# TransientsControls.net
KiCad netlist of a schematic drawn in EAGLE
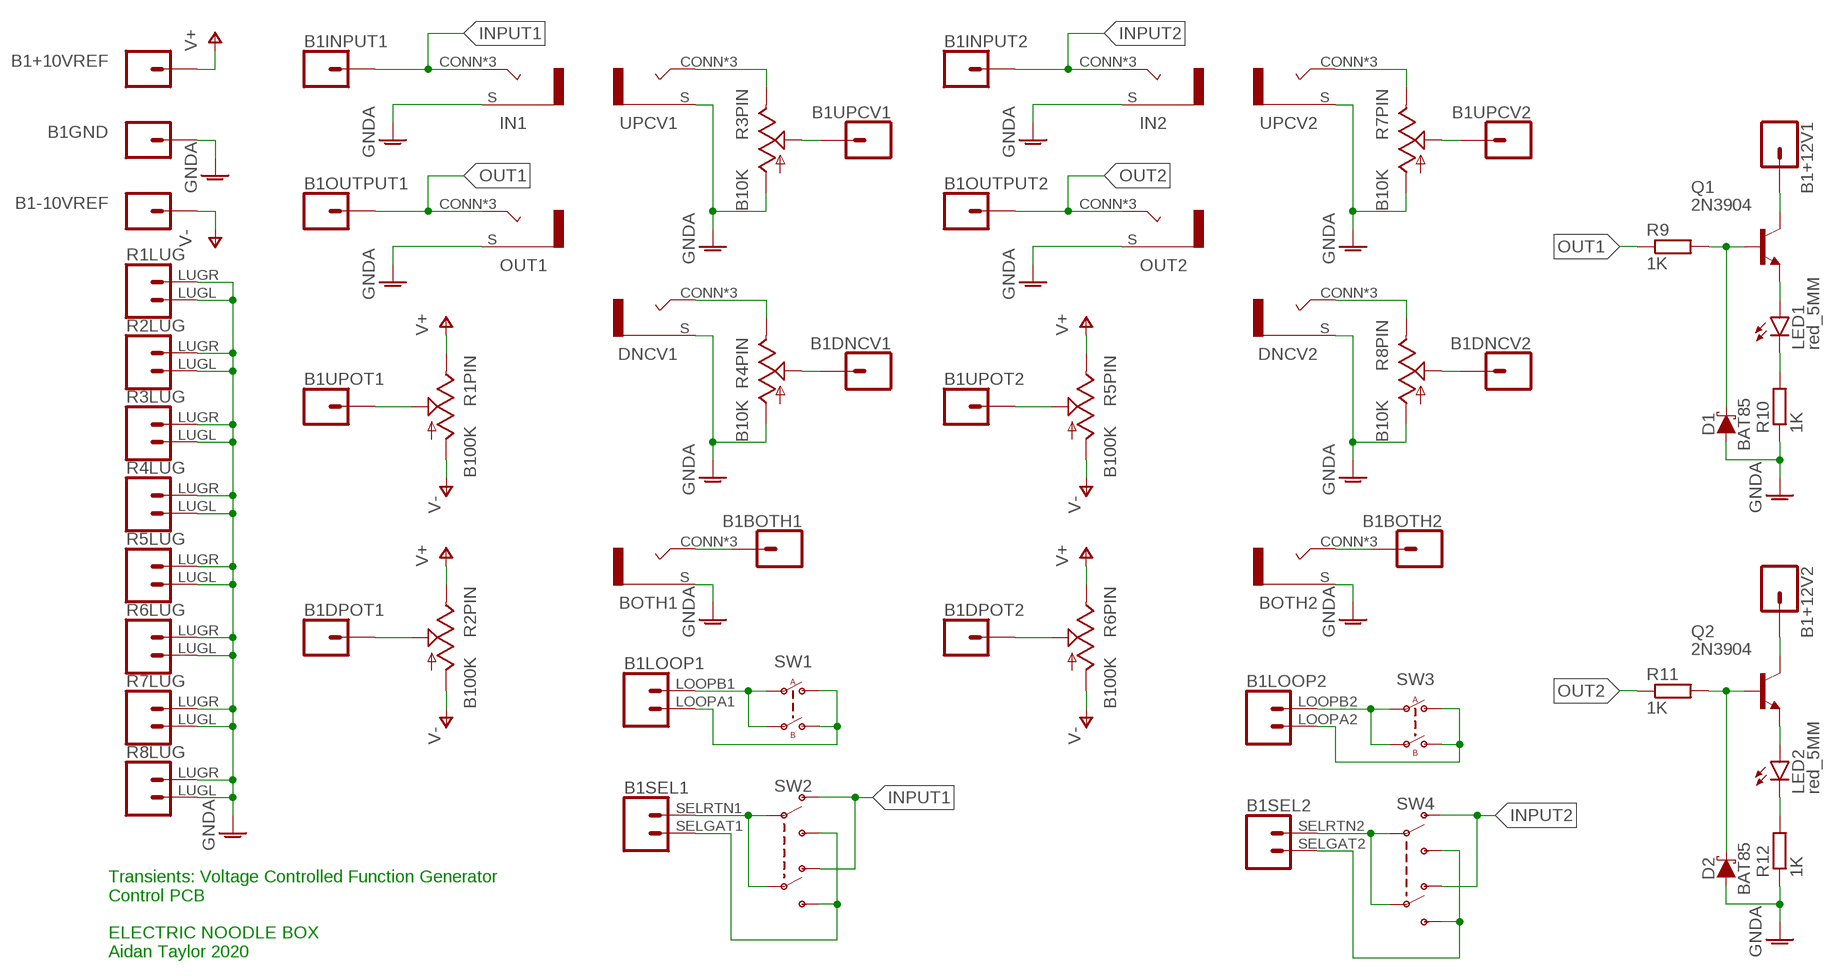
[diagram p0: schematic, sheet 1]

(export (version "E")
  (design (tool "Eeschema 10.0.6"))
  (components
    (comp (ref "B1")
      (value "TRANSIENTS_LINK")
      (footprint "eagle-import:TRANSIENTS")
      (libsource (lib "eagle-import") (part "TRANSIENTS_LINK"))
    )
    (comp (ref "BOTH1")
      (value "COMBI-JACKCINCHNANA")
      (footprint "eagle-import:NEWCOMBOJACK_PANEL")
      (libsource (lib "eagle-import") (part "COMBI-JACKCINCHNANA"))
    )
    (comp (ref "BOTH2")
      (value "COMBI-JACKCINCHNANA")
      (footprint "eagle-import:NEWCOMBOJACK_PANEL")
      (libsource (lib "eagle-import") (part "COMBI-JACKCINCHNANA"))
    )
    (comp (ref "D1")
      (value "BAT85")
      (footprint "eagle-import:DO35-7")
      (libsource (lib "eagle-import") (part "SCHOTTKY_DO35"))
    )
    (comp (ref "D2")
      (value "BAT85")
      (footprint "eagle-import:DO35-7")
      (libsource (lib "eagle-import") (part "SCHOTTKY_DO35"))
    )
    (comp (ref "DNCV1")
      (value "COMBI-JACKCINCHNANA")
      (footprint "eagle-import:NEWCOMBOJACK_PANEL")
      (libsource (lib "eagle-import") (part "COMBI-JACKCINCHNANA"))
    )
    (comp (ref "DNCV2")
      (value "COMBI-JACKCINCHNANA")
      (footprint "eagle-import:NEWCOMBOJACK_PANEL")
      (libsource (lib "eagle-import") (part "COMBI-JACKCINCHNANA"))
    )
    (comp (ref "IN1")
      (value "COMBI-JACKCINCHNANA")
      (footprint "eagle-import:NEWCOMBOJACK_PANEL")
      (libsource (lib "eagle-import") (part "COMBI-JACKCINCHNANA"))
    )
    (comp (ref "IN2")
      (value "COMBI-JACKCINCHNANA")
      (footprint "eagle-import:NEWCOMBOJACK_PANEL")
      (libsource (lib "eagle-import") (part "COMBI-JACKCINCHNANA"))
    )
    (comp (ref "LED1")
      (value "red_5MM")
      (footprint "eagle-import:LED5MM")
      (libsource (lib "eagle-import") (part "LED5MM"))
    )
    (comp (ref "LED2")
      (value "red_5MM")
      (footprint "eagle-import:LED5MM")
      (libsource (lib "eagle-import") (part "LED5MM"))
    )
    (comp (ref "OUT1")
      (value "COMBI-JACKCINCHNANA")
      (footprint "eagle-import:NEWCOMBOJACK_PANEL")
      (libsource (lib "eagle-import") (part "COMBI-JACKCINCHNANA"))
    )
    (comp (ref "OUT2")
      (value "COMBI-JACKCINCHNANA")
      (footprint "eagle-import:NEWCOMBOJACK_PANEL")
      (libsource (lib "eagle-import") (part "COMBI-JACKCINCHNANA"))
    )
    (comp (ref "Q1")
      (value "2N3904")
      (footprint "eagle-import:TO92")
      (libsource (lib "eagle-import") (part "2N3904"))
    )
    (comp (ref "Q2")
      (value "2N3904")
      (footprint "eagle-import:TO92")
      (libsource (lib "eagle-import") (part "2N3904"))
    )
    (comp (ref "R1")
      (value "B100K")
      (footprint "eagle-import:ALPHA_RV09_9MMPOT")
      (libsource (lib "eagle-import") (part "POTENTIOMETER"))
    )
    (comp (ref "R2")
      (value "B100K")
      (footprint "eagle-import:ALPHA_RV09_9MMPOT")
      (libsource (lib "eagle-import") (part "POTENTIOMETER"))
    )
    (comp (ref "R3")
      (value "B10K")
      (footprint "eagle-import:ALPHA_RV09_9MMPOT")
      (libsource (lib "eagle-import") (part "POTENTIOMETER"))
    )
    (comp (ref "R4")
      (value "B10K")
      (footprint "eagle-import:ALPHA_RV09_9MMPOT")
      (libsource (lib "eagle-import") (part "POTENTIOMETER"))
    )
    (comp (ref "R5")
      (value "B100K")
      (footprint "eagle-import:ALPHA_RV09_9MMPOT")
      (libsource (lib "eagle-import") (part "POTENTIOMETER"))
    )
    (comp (ref "R6")
      (value "B100K")
      (footprint "eagle-import:ALPHA_RV09_9MMPOT")
      (libsource (lib "eagle-import") (part "POTENTIOMETER"))
    )
    (comp (ref "R7")
      (value "B10K")
      (footprint "eagle-import:ALPHA_RV09_9MMPOT")
      (libsource (lib "eagle-import") (part "POTENTIOMETER"))
    )
    (comp (ref "R8")
      (value "B10K")
      (footprint "eagle-import:ALPHA_RV09_9MMPOT")
      (libsource (lib "eagle-import") (part "POTENTIOMETER"))
    )
    (comp (ref "R9")
      (value "1K")
      (footprint "eagle-import:0207_10")
      (libsource (lib "eagle-import") (part "R-EU_0207/10"))
    )
    (comp (ref "R10")
      (value "1K")
      (footprint "eagle-import:0207_10")
      (libsource (lib "eagle-import") (part "R-EU_0207/10"))
    )
    (comp (ref "R11")
      (value "1K")
      (footprint "eagle-import:0207_10")
      (libsource (lib "eagle-import") (part "R-EU_0207/10"))
    )
    (comp (ref "R12")
      (value "1K")
      (footprint "eagle-import:0207_10")
      (libsource (lib "eagle-import") (part "R-EU_0207/10"))
    )
    (comp (ref "SW1")
      (value "PVA1_DPST")
      (footprint "eagle-import:PVA1_PUSHBUTTON")
      (libsource (lib "eagle-import") (part "PVA1_DPST"))
    )
    (comp (ref "SW2")
      (value "PVA2_DPDT")
      (footprint "eagle-import:PVA2_PUSHBUTTON")
      (libsource (lib "eagle-import") (part "PVA2_DPDT"))
    )
    (comp (ref "SW3")
      (value "PVA1_DPST")
      (footprint "eagle-import:PVA1_PUSHBUTTON")
      (libsource (lib "eagle-import") (part "PVA1_DPST"))
    )
    (comp (ref "SW4")
      (value "PVA2_DPDT")
      (footprint "eagle-import:PVA2_PUSHBUTTON")
      (libsource (lib "eagle-import") (part "PVA2_DPDT"))
    )
    (comp (ref "UPCV1")
      (value "COMBI-JACKCINCHNANA")
      (footprint "eagle-import:NEWCOMBOJACK_PANEL")
      (libsource (lib "eagle-import") (part "COMBI-JACKCINCHNANA"))
    )
    (comp (ref "UPCV2")
      (value "COMBI-JACKCINCHNANA")
      (footprint "eagle-import:NEWCOMBOJACK_PANEL")
      (libsource (lib "eagle-import") (part "COMBI-JACKCINCHNANA"))
    )
  )
  (nets
    (net (code "1") (name "GNDA") (class "Default")
      (node (ref "B1") (pin "GND1") (pinfunction "1_GND1") (pintype "passive"))
      (node (ref "B1") (pin "GND2") (pinfunction "1_GND2") (pintype "passive"))
      (node (ref "BOTH1") (pin "S") (pinfunction "S_S") (pintype "passive"))
      (node (ref "BOTH2") (pin "S") (pinfunction "S_S") (pintype "passive"))
      (node (ref "D1") (pin "A") (pinfunction "A_A") (pintype "passive"))
      (node (ref "D2") (pin "A") (pinfunction "A_A") (pintype "passive"))
      (node (ref "DNCV1") (pin "S") (pinfunction "S_S") (pintype "passive"))
      (node (ref "DNCV2") (pin "S") (pinfunction "S_S") (pintype "passive"))
      (node (ref "IN1") (pin "S") (pinfunction "S_S") (pintype "passive"))
      (node (ref "IN2") (pin "S") (pinfunction "S_S") (pintype "passive"))
      (node (ref "OUT1") (pin "S") (pinfunction "S_S") (pintype "passive"))
      (node (ref "OUT2") (pin "S") (pinfunction "S_S") (pintype "passive"))
      (node (ref "R1") (pin "LUGL") (pinfunction "1_LUGL") (pintype "passive"))
      (node (ref "R1") (pin "LUGR") (pinfunction "2_LUGR") (pintype "passive"))
      (node (ref "R10") (pin "1") (pinfunction "1_1") (pintype "passive"))
      (node (ref "R12") (pin "1") (pinfunction "1_1") (pintype "passive"))
      (node (ref "R2") (pin "LUGL") (pinfunction "1_LUGL") (pintype "passive"))
      (node (ref "R2") (pin "LUGR") (pinfunction "2_LUGR") (pintype "passive"))
      (node (ref "R3") (pin "C1") (pinfunction "A_C1") (pintype "passive"))
      (node (ref "R3") (pin "LUGL") (pinfunction "1_LUGL") (pintype "passive"))
      (node (ref "R3") (pin "LUGR") (pinfunction "2_LUGR") (pintype "passive"))
      (node (ref "R4") (pin "C1") (pinfunction "A_C1") (pintype "passive"))
      (node (ref "R4") (pin "LUGL") (pinfunction "1_LUGL") (pintype "passive"))
      (node (ref "R4") (pin "LUGR") (pinfunction "2_LUGR") (pintype "passive"))
      (node (ref "R5") (pin "LUGL") (pinfunction "1_LUGL") (pintype "passive"))
      (node (ref "R5") (pin "LUGR") (pinfunction "2_LUGR") (pintype "passive"))
      (node (ref "R6") (pin "LUGL") (pinfunction "1_LUGL") (pintype "passive"))
      (node (ref "R6") (pin "LUGR") (pinfunction "2_LUGR") (pintype "passive"))
      (node (ref "R7") (pin "C1") (pinfunction "A_C1") (pintype "passive"))
      (node (ref "R7") (pin "LUGL") (pinfunction "1_LUGL") (pintype "passive"))
      (node (ref "R7") (pin "LUGR") (pinfunction "2_LUGR") (pintype "passive"))
      (node (ref "R8") (pin "C1") (pinfunction "A_C1") (pintype "passive"))
      (node (ref "R8") (pin "LUGL") (pinfunction "1_LUGL") (pintype "passive"))
      (node (ref "R8") (pin "LUGR") (pinfunction "2_LUGR") (pintype "passive"))
      (node (ref "UPCV1") (pin "S") (pinfunction "S_S") (pintype "passive"))
      (node (ref "UPCV2") (pin "S") (pinfunction "S_S") (pintype "passive"))
    )
    (net (code "2") (name "INPUT1") (class "Default")
      (node (ref "B1") (pin "IN1") (pinfunction "1_IN1") (pintype "passive"))
      (node (ref "IN1") (pin "CONN") (pinfunction "T_CONN") (pintype "passive"))
      (node (ref "IN1") (pin "T1") (pinfunction "T_T1") (pintype "passive"))
      (node (ref "IN1") (pin "T2") (pinfunction "T_T2") (pintype "passive"))
      (node (ref "SW2") (pin "SWA2") (pinfunction "SW1_3_SWA2") (pintype "passive"))
      (node (ref "SW2") (pin "SWB2") (pinfunction "SW2_3_SWB2") (pintype "passive"))
    )
    (net (code "3") (name "INPUT2") (class "Default")
      (node (ref "B1") (pin "INPUT2") (pinfunction "1_INPUT2") (pintype "passive"))
      (node (ref "IN2") (pin "CONN") (pinfunction "T_CONN") (pintype "passive"))
      (node (ref "IN2") (pin "T1") (pinfunction "T_T1") (pintype "passive"))
      (node (ref "IN2") (pin "T2") (pinfunction "T_T2") (pintype "passive"))
      (node (ref "SW4") (pin "SWA2") (pinfunction "SW1_3_SWA2") (pintype "passive"))
      (node (ref "SW4") (pin "SWB2") (pinfunction "SW2_3_SWB2") (pintype "passive"))
    )
    (net (code "4") (name "Net-(B1B-1)") (class "Default")
      (node (ref "B1") (pin "+12V1") (pinfunction "1_+12V1") (pintype "passive"))
      (node (ref "Q1") (pin "1") (pinfunction "C_1") (pintype "passive"))
    )
    (net (code "5") (name "Net-(B1C-1)") (class "Default")
      (node (ref "B1") (pin "+12V2") (pinfunction "1_+12V2") (pintype "passive"))
      (node (ref "Q2") (pin "1") (pinfunction "C_1") (pintype "passive"))
    )
    (net (code "6") (name "Net-(B1E-1)") (class "Default")
      (node (ref "B1") (pin "BOTH1") (pinfunction "1_BOTH1") (pintype "passive"))
      (node (ref "BOTH1") (pin "CONN") (pinfunction "T_CONN") (pintype "passive"))
      (node (ref "BOTH1") (pin "T1") (pinfunction "T_T1") (pintype "passive"))
      (node (ref "BOTH1") (pin "T2") (pinfunction "T_T2") (pintype "passive"))
    )
    (net (code "7") (name "Net-(B1F-1)") (class "Default")
      (node (ref "B1") (pin "BOTH2") (pinfunction "1_BOTH2") (pintype "passive"))
      (node (ref "BOTH2") (pin "CONN") (pinfunction "T_CONN") (pintype "passive"))
      (node (ref "BOTH2") (pin "T1") (pinfunction "T_T1") (pintype "passive"))
      (node (ref "BOTH2") (pin "T2") (pinfunction "T_T2") (pintype "passive"))
    )
    (net (code "8") (name "Net-(B1G-1)") (class "Default")
      (node (ref "B1") (pin "DNCV1") (pinfunction "1_DNCV1") (pintype "passive"))
      (node (ref "R4") (pin "C2") (pinfunction "W_C2") (pintype "passive"))
    )
    (net (code "9") (name "Net-(B1H-1)") (class "Default")
      (node (ref "B1") (pin "DNCV2") (pinfunction "1_DNCV2") (pintype "passive"))
      (node (ref "R8") (pin "C2") (pinfunction "W_C2") (pintype "passive"))
    )
    (net (code "10") (name "Net-(B1I-1)") (class "Default")
      (node (ref "B1") (pin "DPOT1") (pinfunction "1_DPOT1") (pintype "passive"))
      (node (ref "R2") (pin "C2") (pinfunction "W_C2") (pintype "passive"))
    )
    (net (code "11") (name "Net-(B1J-1)") (class "Default")
      (node (ref "B1") (pin "DPOT2") (pinfunction "1_DPOT2") (pintype "passive"))
      (node (ref "R6") (pin "C2") (pinfunction "W_C2") (pintype "passive"))
    )
    (net (code "12") (name "Net-(B1N-1)") (class "Default")
      (node (ref "B1") (pin "LOOPA1") (pinfunction "1_LOOPA1") (pintype "passive"))
      (node (ref "SW1") (pin "SWA2") (pinfunction "SWA2_SWA2") (pintype "passive"))
      (node (ref "SW1") (pin "SWB2") (pinfunction "SWB2_SWB2") (pintype "passive"))
    )
    (net (code "13") (name "Net-(B1N-2)") (class "Default")
      (node (ref "B1") (pin "LOOPB1") (pinfunction "2_LOOPB1") (pintype "passive"))
      (node (ref "SW1") (pin "SWA1") (pinfunction "SWA1_SWA1") (pintype "passive"))
      (node (ref "SW1") (pin "SWB1") (pinfunction "SWB1_SWB1") (pintype "passive"))
    )
    (net (code "14") (name "Net-(B1O-1)") (class "Default")
      (node (ref "B1") (pin "LOOPA2") (pinfunction "1_LOOPA2") (pintype "passive"))
      (node (ref "SW3") (pin "SWA2") (pinfunction "SWA2_SWA2") (pintype "passive"))
      (node (ref "SW3") (pin "SWB2") (pinfunction "SWB2_SWB2") (pintype "passive"))
    )
    (net (code "15") (name "Net-(B1O-2)") (class "Default")
      (node (ref "B1") (pin "LOOPB2") (pinfunction "2_LOOPB2") (pintype "passive"))
      (node (ref "SW3") (pin "SWA1") (pinfunction "SWA1_SWA1") (pintype "passive"))
      (node (ref "SW3") (pin "SWB1") (pinfunction "SWB1_SWB1") (pintype "passive"))
    )
    (net (code "16") (name "Net-(B1T-1)") (class "Default")
      (node (ref "B1") (pin "SELGAT1") (pinfunction "1_SELGAT1") (pintype "passive"))
      (node (ref "SW2") (pin "SWA1") (pinfunction "SW1_1_SWA1") (pintype "passive"))
      (node (ref "SW2") (pin "SWB1") (pinfunction "SW2_1_SWB1") (pintype "passive"))
    )
    (net (code "17") (name "Net-(B1T-2)") (class "Default")
      (node (ref "B1") (pin "SELRTN1") (pinfunction "2_SELRTN1") (pintype "passive"))
      (node (ref "SW2") (pin "SWA0") (pinfunction "SW1_2_SWA0") (pintype "passive"))
      (node (ref "SW2") (pin "SWB0") (pinfunction "SW2_2_SWB0") (pintype "passive"))
    )
    (net (code "18") (name "Net-(B1U-1)") (class "Default")
      (node (ref "B1") (pin "SELGAT2") (pinfunction "1_SELGAT2") (pintype "passive"))
      (node (ref "SW4") (pin "SWA1") (pinfunction "SW1_1_SWA1") (pintype "passive"))
      (node (ref "SW4") (pin "SWB1") (pinfunction "SW2_1_SWB1") (pintype "passive"))
    )
    (net (code "19") (name "Net-(B1U-2)") (class "Default")
      (node (ref "B1") (pin "SELRTN2") (pinfunction "2_SELRTN2") (pintype "passive"))
      (node (ref "SW4") (pin "SWA0") (pinfunction "SW1_2_SWA0") (pintype "passive"))
      (node (ref "SW4") (pin "SWB0") (pinfunction "SW2_2_SWB0") (pintype "passive"))
    )
    (net (code "20") (name "Net-(B1V-1)") (class "Default")
      (node (ref "B1") (pin "UPCV1") (pinfunction "1_UPCV1") (pintype "passive"))
      (node (ref "R3") (pin "C2") (pinfunction "W_C2") (pintype "passive"))
    )
    (net (code "21") (name "Net-(B1W-1)") (class "Default")
      (node (ref "B1") (pin "UPCV2") (pinfunction "1_UPCV2") (pintype "passive"))
      (node (ref "R7") (pin "C2") (pinfunction "W_C2") (pintype "passive"))
    )
    (net (code "22") (name "Net-(B1X-1)") (class "Default")
      (node (ref "B1") (pin "UPOT1") (pinfunction "1_UPOT1") (pintype "passive"))
      (node (ref "R1") (pin "C2") (pinfunction "W_C2") (pintype "passive"))
    )
    (net (code "23") (name "Net-(B1Y-1)") (class "Default")
      (node (ref "B1") (pin "UPOT2") (pinfunction "1_UPOT2") (pintype "passive"))
      (node (ref "R5") (pin "C2") (pinfunction "W_C2") (pintype "passive"))
    )
    (net (code "24") (name "Net-(LED1-C)") (class "Default")
      (node (ref "LED1") (pin "K") (pinfunction "C_K") (pintype "passive"))
      (node (ref "R10") (pin "2") (pinfunction "2_2") (pintype "passive"))
    )
    (net (code "25") (name "Net-(LED2-C)") (class "Default")
      (node (ref "LED2") (pin "K") (pinfunction "C_K") (pintype "passive"))
      (node (ref "R12") (pin "2") (pinfunction "2_2") (pintype "passive"))
    )
    (net (code "26") (name "Net-(Q1-B)") (class "Default")
      (node (ref "D1") (pin "C") (pinfunction "C_C") (pintype "passive"))
      (node (ref "Q1") (pin "2") (pinfunction "B_2") (pintype "passive"))
      (node (ref "R9") (pin "2") (pinfunction "2_2") (pintype "passive"))
    )
    (net (code "27") (name "Net-(Q1-E)") (class "Default")
      (node (ref "LED1") (pin "A") (pinfunction "A_A") (pintype "passive"))
      (node (ref "Q1") (pin "3") (pinfunction "E_3") (pintype "passive"))
    )
    (net (code "28") (name "Net-(Q2-B)") (class "Default")
      (node (ref "D2") (pin "C") (pinfunction "C_C") (pintype "passive"))
      (node (ref "Q2") (pin "2") (pinfunction "B_2") (pintype "passive"))
      (node (ref "R11") (pin "2") (pinfunction "2_2") (pintype "passive"))
    )
    (net (code "29") (name "Net-(Q2-E)") (class "Default")
      (node (ref "LED2") (pin "A") (pinfunction "A_A") (pintype "passive"))
      (node (ref "Q2") (pin "3") (pinfunction "E_3") (pintype "passive"))
    )
    (net (code "30") (name "Net-(R3B-B)") (class "Default")
      (node (ref "R3") (pin "C3") (pinfunction "B_C3") (pintype "passive"))
      (node (ref "UPCV1") (pin "CONN") (pinfunction "T_CONN") (pintype "passive"))
      (node (ref "UPCV1") (pin "T1") (pinfunction "T_T1") (pintype "passive"))
      (node (ref "UPCV1") (pin "T2") (pinfunction "T_T2") (pintype "passive"))
    )
    (net (code "31") (name "Net-(R4B-B)") (class "Default")
      (node (ref "DNCV1") (pin "CONN") (pinfunction "T_CONN") (pintype "passive"))
      (node (ref "DNCV1") (pin "T1") (pinfunction "T_T1") (pintype "passive"))
      (node (ref "DNCV1") (pin "T2") (pinfunction "T_T2") (pintype "passive"))
      (node (ref "R4") (pin "C3") (pinfunction "B_C3") (pintype "passive"))
    )
    (net (code "32") (name "Net-(R7B-B)") (class "Default")
      (node (ref "R7") (pin "C3") (pinfunction "B_C3") (pintype "passive"))
      (node (ref "UPCV2") (pin "CONN") (pinfunction "T_CONN") (pintype "passive"))
      (node (ref "UPCV2") (pin "T1") (pinfunction "T_T1") (pintype "passive"))
      (node (ref "UPCV2") (pin "T2") (pinfunction "T_T2") (pintype "passive"))
    )
    (net (code "33") (name "Net-(R8B-B)") (class "Default")
      (node (ref "DNCV2") (pin "CONN") (pinfunction "T_CONN") (pintype "passive"))
      (node (ref "DNCV2") (pin "T1") (pinfunction "T_T1") (pintype "passive"))
      (node (ref "DNCV2") (pin "T2") (pinfunction "T_T2") (pintype "passive"))
      (node (ref "R8") (pin "C3") (pinfunction "B_C3") (pintype "passive"))
    )
    (net (code "34") (name "OUT1") (class "Default")
      (node (ref "B1") (pin "OUT1") (pinfunction "1_OUT1") (pintype "passive"))
      (node (ref "OUT1") (pin "CONN") (pinfunction "T_CONN") (pintype "passive"))
      (node (ref "OUT1") (pin "T1") (pinfunction "T_T1") (pintype "passive"))
      (node (ref "OUT1") (pin "T2") (pinfunction "T_T2") (pintype "passive"))
      (node (ref "R9") (pin "1") (pinfunction "1_1") (pintype "passive"))
    )
    (net (code "35") (name "OUT2") (class "Default")
      (node (ref "B1") (pin "OUT2") (pinfunction "1_OUT2") (pintype "passive"))
      (node (ref "OUT2") (pin "CONN") (pinfunction "T_CONN") (pintype "passive"))
      (node (ref "OUT2") (pin "T1") (pinfunction "T_T1") (pintype "passive"))
      (node (ref "OUT2") (pin "T2") (pinfunction "T_T2") (pintype "passive"))
      (node (ref "R11") (pin "1") (pinfunction "1_1") (pintype "passive"))
    )
    (net (code "36") (name "V+") (class "Default")
      (node (ref "B1") (pin "+10VR1") (pinfunction "1_+10VR1") (pintype "passive"))
      (node (ref "B1") (pin "+10VR2") (pinfunction "1_+10VR2") (pintype "passive"))
      (node (ref "R1") (pin "C3") (pinfunction "B_C3") (pintype "passive"))
      (node (ref "R2") (pin "C3") (pinfunction "B_C3") (pintype "passive"))
      (node (ref "R5") (pin "C3") (pinfunction "B_C3") (pintype "passive"))
      (node (ref "R6") (pin "C3") (pinfunction "B_C3") (pintype "passive"))
    )
    (net (code "37") (name "V-") (class "Default")
      (node (ref "B1") (pin "-10VR1") (pinfunction "1_-10VR1") (pintype "passive"))
      (node (ref "B1") (pin "-10VR2") (pinfunction "1_-10VR2") (pintype "passive"))
      (node (ref "R1") (pin "C1") (pinfunction "A_C1") (pintype "passive"))
      (node (ref "R2") (pin "C1") (pinfunction "A_C1") (pintype "passive"))
      (node (ref "R5") (pin "C1") (pinfunction "A_C1") (pintype "passive"))
      (node (ref "R6") (pin "C1") (pinfunction "A_C1") (pintype "passive"))
    )
  )
)
